# DRV2605L.net
KiCad netlist of a schematic drawn in Altium Designer
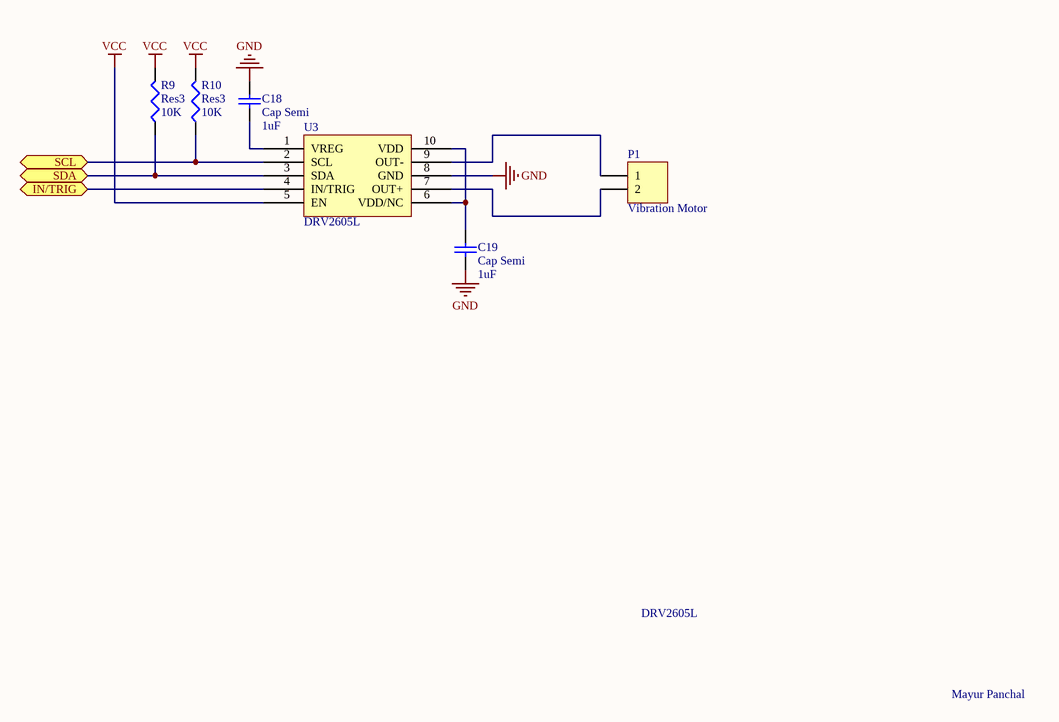
[diagram p0: DRV2605L.SchDoc]

(export (version "E")
  (design (tool "Eeschema 10.0.6"))
  (components
    (comp (ref "C18")
      (value "Cap Semi")
      (footprint "1608[0603]")
      (description "Capacitor (Semiconductor SIM Model)")
      (fields (field (name "ALTIUM_VALUE") "1uF") (field (name "PUBLISHER") "Altium Limited"))
      (libsource (lib "Miscellaneous Devices") (part "Cap Semi"))
    )
    (comp (ref "C19")
      (value "Cap Semi")
      (footprint "1608[0603]")
      (description "Capacitor (Semiconductor SIM Model)")
      (fields (field (name "ALTIUM_VALUE") "1uF") (field (name "PUBLISHER") "Altium Limited"))
      (libsource (lib "Miscellaneous Devices") (part "Cap Semi"))
    )
    (comp (ref "P1")
      (value "Vibration Motor")
      (footprint "HDR1X2")
      (description "Header, 2-Pin")
      (fields (field (name "PUBLISHER") "Altium Limited"))
      (libsource (lib "Miscellaneous Connectors") (part "Header 2"))
    )
    (comp (ref "R9")
      (value "Res3")
      (footprint "J1-0603")
      (description "Resistor")
      (fields (field (name "ALTIUM_VALUE") "10K") (field (name "PUBLISHER") "Altium Limited"))
      (libsource (lib "Miscellaneous Devices") (part "Res3"))
    )
    (comp (ref "R10")
      (value "Res3")
      (footprint "J1-0603")
      (description "Resistor")
      (fields (field (name "ALTIUM_VALUE") "10K") (field (name "PUBLISHER") "Altium Limited"))
      (libsource (lib "Miscellaneous Devices") (part "Res3"))
    )
    (comp (ref "U3")
      (value "DRV2605L")
      (footprint "DRV2605L")
      (libsource (lib "Custom Parts") (part "DRV2605L"))
    )
  )
  (nets
    (net (code "1") (name "/IN{slash}TRIG") (class "Default")
      (node (ref "U3") (pin "4") (pinfunction "IN/TRIG_4") (pintype "passive"))
    )
    (net (code "2") (name "/SCL") (class "Default")
      (node (ref "R10") (pin "1") (pinfunction "1_1") (pintype "passive"))
      (node (ref "U3") (pin "2") (pinfunction "SCL_2") (pintype "passive"))
    )
    (net (code "3") (name "/SDA") (class "Default")
      (node (ref "R9") (pin "1") (pinfunction "1_1") (pintype "passive"))
      (node (ref "U3") (pin "3") (pinfunction "SDA_3") (pintype "passive"))
    )
    (net (code "4") (name "GND") (class "Default")
      (node (ref "C18") (pin "2") (pinfunction "2_2") (pintype "passive"))
      (node (ref "C19") (pin "1") (pinfunction "1_1") (pintype "passive"))
      (node (ref "U3") (pin "8") (pinfunction "GND_8") (pintype "passive"))
    )
    (net (code "5") (name "Net-(U3-OUT+)") (class "Default")
      (node (ref "P1") (pin "2") (pinfunction "2_2") (pintype "passive"))
      (node (ref "U3") (pin "7") (pinfunction "OUT+_7") (pintype "passive"))
    )
    (net (code "6") (name "Net-(U3-OUT-)") (class "Default")
      (node (ref "P1") (pin "1") (pinfunction "1_1") (pintype "passive"))
      (node (ref "U3") (pin "9") (pinfunction "OUT-_9") (pintype "passive"))
    )
    (net (code "7") (name "Net-(U3-VDD)") (class "Default")
      (node (ref "C19") (pin "2") (pinfunction "2_2") (pintype "passive"))
      (node (ref "U3") (pin "10") (pinfunction "VDD_10") (pintype "passive"))
      (node (ref "U3") (pin "6") (pinfunction "VDD/NC_6") (pintype "passive"))
    )
    (net (code "8") (name "Net-(U3-VREG)") (class "Default")
      (node (ref "C18") (pin "1") (pinfunction "1_1") (pintype "passive"))
      (node (ref "U3") (pin "1") (pinfunction "VREG_1") (pintype "passive"))
    )
    (net (code "9") (name "VCC") (class "Default")
      (node (ref "R10") (pin "2") (pinfunction "2_2") (pintype "passive"))
      (node (ref "R9") (pin "2") (pinfunction "2_2") (pintype "passive"))
      (node (ref "U3") (pin "5") (pinfunction "EN_5") (pintype "passive"))
    )
  )
)
